# GPS_Module_2.net
KiCad netlist of a schematic drawn in EAGLE
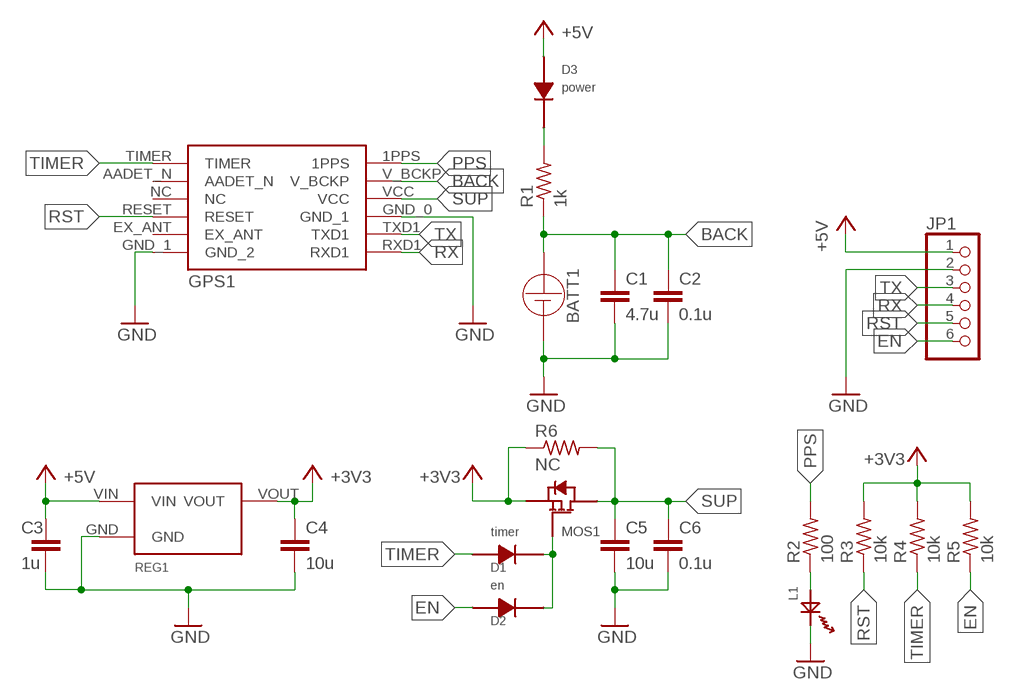
[diagram p0: schematic, sheet 1]

(export (version "E")
  (design (tool "Eeschema 10.0.6"))
  (components
    (comp (ref "BATT1")
      (value "CR2032_PLATE")
      (footprint "eagle-import:CR2032_PLATE")
      (libsource (lib "eagle-import") (part "CR2032_PLATE"))
    )
    (comp (ref "C1")
      (value "4.7u")
      (footprint "eagle-import:C0603")
      (libsource (lib "eagle-import") (part "C-EUC0603"))
    )
    (comp (ref "C2")
      (value "0.1u")
      (footprint "eagle-import:C0603")
      (libsource (lib "eagle-import") (part "C-EUC0603"))
    )
    (comp (ref "C3")
      (value "1u")
      (footprint "eagle-import:C0603")
      (libsource (lib "eagle-import") (part "C-EUC0603"))
    )
    (comp (ref "C4")
      (value "10u")
      (footprint "eagle-import:C0603")
      (libsource (lib "eagle-import") (part "C-EUC0603"))
    )
    (comp (ref "C5")
      (value "10u")
      (footprint "eagle-import:C0603")
      (libsource (lib "eagle-import") (part "C-EUC0603"))
    )
    (comp (ref "C6")
      (value "0.1u")
      (footprint "eagle-import:C0603")
      (libsource (lib "eagle-import") (part "C-EUC0603"))
    )
    (comp (ref "D1")
      (value "timer")
      (footprint "eagle-import:SOD-123")
      (libsource (lib "eagle-import") (part "1W4148W"))
    )
    (comp (ref "D2")
      (value "en")
      (footprint "eagle-import:SOD-123")
      (libsource (lib "eagle-import") (part "1W4148W"))
    )
    (comp (ref "D3")
      (value "power")
      (footprint "eagle-import:SOD-123FL")
      (libsource (lib "eagle-import") (part "SS2040FL"))
    )
    (comp (ref "GPS1")
      (value "L80-M39")
      (footprint "eagle-import:L80")
      (libsource (lib "eagle-import") (part "L80-M39"))
    )
    (comp (ref "JP1")
      (value "PINHD-1X6")
      (footprint "eagle-import:1X06")
      (libsource (lib "eagle-import") (part "PINHD-1X6"))
    )
    (comp (ref "L1")
      (value "OSXX1608C1A")
      (footprint "eagle-import:OSXX1608C1A")
      (libsource (lib "eagle-import") (part "OSXX1608C1A"))
    )
    (comp (ref "MOS1")
      (value "AO3401A")
      (footprint "eagle-import:SOT-23")
      (libsource (lib "eagle-import") (part "AO3401A"))
    )
    (comp (ref "R1")
      (value "1k")
      (footprint "eagle-import:R0603")
      (libsource (lib "eagle-import") (part "R-US_R0603"))
    )
    (comp (ref "R2")
      (value "100")
      (footprint "eagle-import:R0603")
      (libsource (lib "eagle-import") (part "R-US_R0603"))
    )
    (comp (ref "R3")
      (value "10k")
      (footprint "eagle-import:R0603")
      (libsource (lib "eagle-import") (part "R-US_R0603"))
    )
    (comp (ref "R4")
      (value "10k")
      (footprint "eagle-import:R0603")
      (libsource (lib "eagle-import") (part "R-US_R0603"))
    )
    (comp (ref "R5")
      (value "10k")
      (footprint "eagle-import:R0603")
      (libsource (lib "eagle-import") (part "R-US_R0603"))
    )
    (comp (ref "R6")
      (value "NC")
      (footprint "eagle-import:R0603")
      (libsource (lib "eagle-import") (part "R-US_R0603"))
    )
    (comp (ref "REG1")
      (value "AP7375")
      (footprint "eagle-import:SOT23")
      (libsource (lib "eagle-import") (part "AP7375"))
    )
  )
  (nets
    (net (code "1") (name "+3V3") (class "Default")
      (node (ref "C4") (pin "1") (pinfunction "1_1") (pintype "passive"))
      (node (ref "MOS1") (pin "S") (pinfunction "S_S") (pintype "bidirectional"))
      (node (ref "R3") (pin "2") (pinfunction "2_2") (pintype "passive"))
      (node (ref "R4") (pin "2") (pinfunction "2_2") (pintype "passive"))
      (node (ref "R5") (pin "2") (pinfunction "2_2") (pintype "passive"))
      (node (ref "R6") (pin "1") (pinfunction "1_1") (pintype "passive"))
      (node (ref "REG1") (pin "VOUT") (pinfunction "VOUT_VOUT") (pintype "bidirectional"))
    )
    (net (code "2") (name "+5V") (class "Default")
      (node (ref "C3") (pin "1") (pinfunction "1_1") (pintype "passive"))
      (node (ref "D3") (pin "C") (pinfunction "C_C") (pintype "bidirectional"))
      (node (ref "JP1") (pin "1") (pinfunction "1_1") (pintype "passive"))
      (node (ref "REG1") (pin "VIN") (pinfunction "VIN_VIN") (pintype "bidirectional"))
    )
    (net (code "3") (name "BACK") (class "Default")
      (node (ref "BATT1") (pin "VCC") (pinfunction "VCC_VCC") (pintype "bidirectional"))
      (node (ref "C1") (pin "1") (pinfunction "1_1") (pintype "passive"))
      (node (ref "C2") (pin "1") (pinfunction "1_1") (pintype "passive"))
      (node (ref "GPS1") (pin "V_BCKP") (pinfunction "V_BCKP_V_BCKP") (pintype "bidirectional"))
      (node (ref "R1") (pin "1") (pinfunction "1_1") (pintype "passive"))
    )
    (net (code "4") (name "EN") (class "Default")
      (node (ref "D2") (pin "C") (pinfunction "C_C") (pintype "bidirectional"))
      (node (ref "JP1") (pin "6") (pinfunction "6_6") (pintype "passive"))
      (node (ref "R5") (pin "1") (pinfunction "1_1") (pintype "passive"))
    )
    (net (code "5") (name "GND") (class "Default")
      (node (ref "BATT1") (pin "GND") (pinfunction "GND_GND") (pintype "bidirectional"))
      (node (ref "C1") (pin "2") (pinfunction "2_2") (pintype "passive"))
      (node (ref "C2") (pin "2") (pinfunction "2_2") (pintype "passive"))
      (node (ref "C3") (pin "2") (pinfunction "2_2") (pintype "passive"))
      (node (ref "C4") (pin "2") (pinfunction "2_2") (pintype "passive"))
      (node (ref "C5") (pin "2") (pinfunction "2_2") (pintype "passive"))
      (node (ref "C6") (pin "2") (pinfunction "2_2") (pintype "passive"))
      (node (ref "GPS1") (pin "GND_0") (pinfunction "GND_1_GND_0") (pintype "bidirectional"))
      (node (ref "GPS1") (pin "GND_1") (pinfunction "GND_2_GND_1") (pintype "bidirectional"))
      (node (ref "JP1") (pin "2") (pinfunction "2_2") (pintype "passive"))
      (node (ref "L1") (pin "CT") (pinfunction "CT_CT") (pintype "bidirectional"))
      (node (ref "REG1") (pin "GND") (pinfunction "GND_GND") (pintype "bidirectional"))
    )
    (net (code "6") (name "Net-(D1-PadA)") (class "Default")
      (node (ref "D1") (pin "A") (pinfunction "A_A") (pintype "bidirectional"))
      (node (ref "D2") (pin "A") (pinfunction "A_A") (pintype "bidirectional"))
      (node (ref "MOS1") (pin "G") (pinfunction "G_G") (pintype "bidirectional"))
    )
    (net (code "7") (name "Net-(D3-PadA)") (class "Default")
      (node (ref "D3") (pin "A") (pinfunction "A_A") (pintype "bidirectional"))
      (node (ref "R1") (pin "2") (pinfunction "2_2") (pintype "passive"))
    )
    (net (code "8") (name "Net-(L1-PadAN)") (class "Default")
      (node (ref "L1") (pin "AN") (pinfunction "AN_AN") (pintype "bidirectional"))
      (node (ref "R2") (pin "1") (pinfunction "1_1") (pintype "passive"))
    )
    (net (code "9") (name "PPS") (class "Default")
      (node (ref "GPS1") (pin "1PPS") (pinfunction "1PPS_1PPS") (pintype "bidirectional"))
      (node (ref "R2") (pin "2") (pinfunction "2_2") (pintype "passive"))
    )
    (net (code "10") (name "RST") (class "Default")
      (node (ref "GPS1") (pin "RESET") (pinfunction "RESET_RESET") (pintype "bidirectional"))
      (node (ref "JP1") (pin "5") (pinfunction "5_5") (pintype "passive"))
      (node (ref "R3") (pin "1") (pinfunction "1_1") (pintype "passive"))
    )
    (net (code "11") (name "RX") (class "Default")
      (node (ref "GPS1") (pin "RXD1") (pinfunction "RXD1_RXD1") (pintype "bidirectional"))
      (node (ref "JP1") (pin "4") (pinfunction "4_4") (pintype "passive"))
    )
    (net (code "12") (name "SUP") (class "Default")
      (node (ref "C5") (pin "1") (pinfunction "1_1") (pintype "passive"))
      (node (ref "C6") (pin "1") (pinfunction "1_1") (pintype "passive"))
      (node (ref "GPS1") (pin "VCC") (pinfunction "VCC_VCC") (pintype "bidirectional"))
      (node (ref "MOS1") (pin "D") (pinfunction "D_D") (pintype "bidirectional"))
      (node (ref "R6") (pin "2") (pinfunction "2_2") (pintype "passive"))
    )
    (net (code "13") (name "TIMER") (class "Default")
      (node (ref "D1") (pin "C") (pinfunction "C_C") (pintype "bidirectional"))
      (node (ref "GPS1") (pin "TIMER") (pinfunction "TIMER_TIMER") (pintype "bidirectional"))
      (node (ref "R4") (pin "1") (pinfunction "1_1") (pintype "passive"))
    )
    (net (code "14") (name "TX") (class "Default")
      (node (ref "GPS1") (pin "TXD1") (pinfunction "TXD1_TXD1") (pintype "bidirectional"))
      (node (ref "JP1") (pin "3") (pinfunction "3_3") (pintype "passive"))
    )
    (net (code "15") (name "unconnected-(GPS1-PadAADET_N)") (class "Default")
      (node (ref "GPS1") (pin "AADET_N") (pinfunction "AADET_N_AADET_N") (pintype "bidirectional"))
    )
    (net (code "16") (name "unconnected-(GPS1-PadEX_ANT)") (class "Default")
      (node (ref "GPS1") (pin "EX_ANT") (pinfunction "EX_ANT_EX_ANT") (pintype "bidirectional"))
    )
    (net (code "17") (name "unconnected-(GPS1-PadNC)") (class "Default")
      (node (ref "GPS1") (pin "NC") (pinfunction "NC_NC") (pintype "bidirectional"))
    )
  )
)
